# 04-CPU_BOARD.net
KiCad netlist of a schematic drawn in Altium Designer
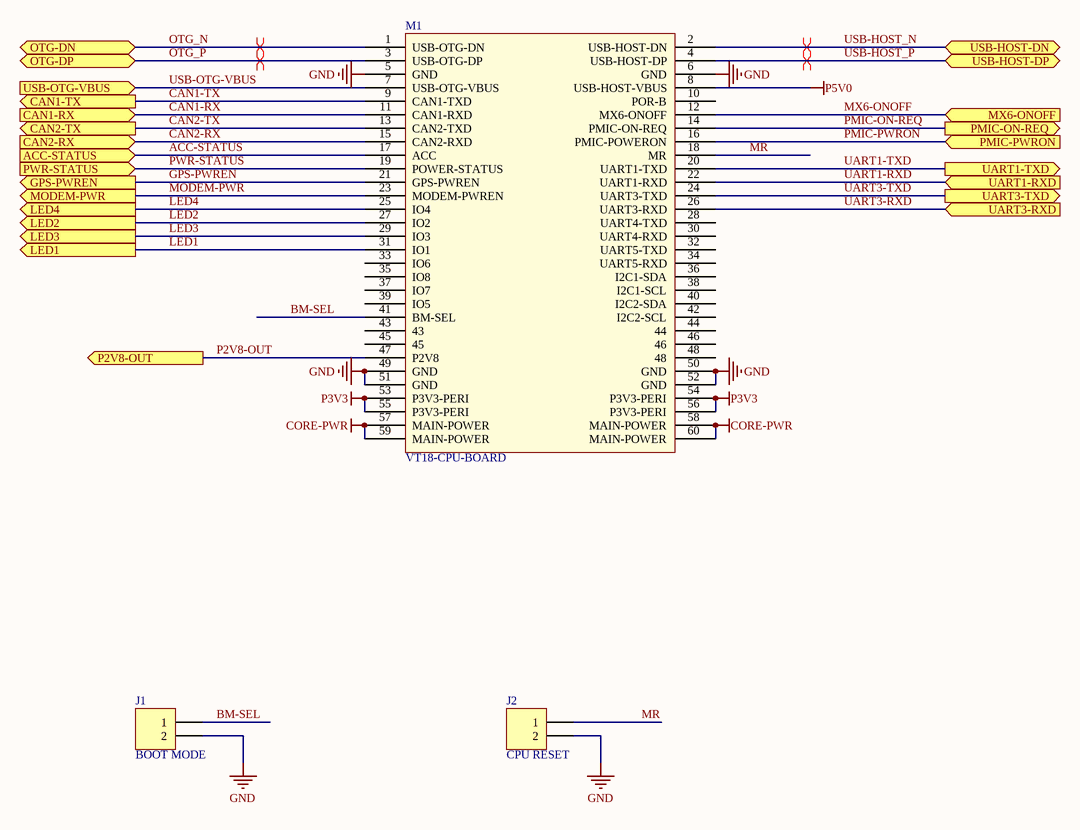
[diagram p0: 04-CPU_BOARD.SchDoc]

(export (version "E")
  (design (tool "Eeschema 10.0.6"))
  (components
    (comp (ref "J1")
      (value "BOOT MODE")
      (footprint "HDR1X2")
      (description "Header, 2-Pin")
      (fields (field (name "PUBLISHER") "Altium Limited"))
      (libsource (lib "Miscellaneous Connectors") (part "Header 2"))
    )
    (comp (ref "J2")
      (value "CPU RESET")
      (footprint "HDR1X2")
      (description "Header, 2-Pin")
      (fields (field (name "PUBLISHER") "Altium Limited"))
      (libsource (lib "Miscellaneous Connectors") (part "Header 2"))
    )
    (comp (ref "M1")
      (value "VT18-CPU-BOARD")
      (footprint "VT18-CPU-BOARD")
      (libsource (lib "Schlib") (part "VT18-CPU-BOARD"))
    )
  )
  (nets
    (net (code "1") (name "/ACC-STATUS") (class "Default")
      (node (ref "M1") (pin "17") (pinfunction "ACC_17") (pintype "passive"))
    )
    (net (code "2") (name "/BM-SEL") (class "Default")
      (node (ref "J1") (pin "1") (pinfunction "1_1") (pintype "passive"))
      (node (ref "M1") (pin "41") (pinfunction "BM-SEL_41") (pintype "passive"))
    )
    (net (code "3") (name "/CAN1-RX") (class "Default")
      (node (ref "M1") (pin "11") (pinfunction "CAN1-RXD_11") (pintype "passive"))
    )
    (net (code "4") (name "/CAN1-TX") (class "Default")
      (node (ref "M1") (pin "9") (pinfunction "CAN1-TXD_9") (pintype "passive"))
    )
    (net (code "5") (name "/CAN2-RX") (class "Default")
      (node (ref "M1") (pin "15") (pinfunction "CAN2-RXD_15") (pintype "passive"))
    )
    (net (code "6") (name "/CAN2-TX") (class "Default")
      (node (ref "M1") (pin "13") (pinfunction "CAN2-TXD_13") (pintype "passive"))
    )
    (net (code "7") (name "/GPS-PWREN") (class "Default")
      (node (ref "M1") (pin "21") (pinfunction "GPS-PWREN_21") (pintype "passive"))
    )
    (net (code "8") (name "/LED1") (class "Default")
      (node (ref "M1") (pin "31") (pinfunction "IO1_31") (pintype "passive"))
    )
    (net (code "9") (name "/LED2") (class "Default")
      (node (ref "M1") (pin "27") (pinfunction "IO2_27") (pintype "passive"))
    )
    (net (code "10") (name "/LED3") (class "Default")
      (node (ref "M1") (pin "29") (pinfunction "IO3_29") (pintype "passive"))
    )
    (net (code "11") (name "/LED4") (class "Default")
      (node (ref "M1") (pin "25") (pinfunction "IO4_25") (pintype "passive"))
    )
    (net (code "12") (name "/MODEM-PWR") (class "Default")
      (node (ref "M1") (pin "23") (pinfunction "MODEM-PWREN_23") (pintype "passive"))
    )
    (net (code "13") (name "/MR") (class "Default")
      (node (ref "J2") (pin "1") (pinfunction "1_1") (pintype "passive"))
      (node (ref "M1") (pin "18") (pinfunction "MR_18") (pintype "passive"))
    )
    (net (code "14") (name "/MX6-ONOFF") (class "Default")
      (node (ref "M1") (pin "12") (pinfunction "MX6-ONOFF_12") (pintype "passive"))
    )
    (net (code "15") (name "/OTG_N") (class "Default")
      (node (ref "M1") (pin "1") (pinfunction "USB-OTG-DN_1") (pintype "passive"))
    )
    (net (code "16") (name "/OTG_P") (class "Default")
      (node (ref "M1") (pin "3") (pinfunction "USB-OTG-DP_3") (pintype "passive"))
    )
    (net (code "17") (name "/P2V8-OUT") (class "Default")
      (node (ref "M1") (pin "47") (pinfunction "P2V8_47") (pintype "passive"))
    )
    (net (code "18") (name "/PMIC-ON-REQ") (class "Default")
      (node (ref "M1") (pin "14") (pinfunction "PMIC-ON-REQ_14") (pintype "passive"))
    )
    (net (code "19") (name "/PMIC-PWRON") (class "Default")
      (node (ref "M1") (pin "16") (pinfunction "PMIC-POWERON_16") (pintype "passive"))
    )
    (net (code "20") (name "/PWR-STATUS") (class "Default")
      (node (ref "M1") (pin "19") (pinfunction "POWER-STATUS_19") (pintype "passive"))
    )
    (net (code "21") (name "/UART1-RXD") (class "Default")
      (node (ref "M1") (pin "22") (pinfunction "UART1-RXD_22") (pintype "passive"))
    )
    (net (code "22") (name "/UART1-TXD") (class "Default")
      (node (ref "M1") (pin "20") (pinfunction "UART1-TXD_20") (pintype "passive"))
    )
    (net (code "23") (name "/UART3-RXD") (class "Default")
      (node (ref "M1") (pin "26") (pinfunction "UART3-RXD_26") (pintype "passive"))
    )
    (net (code "24") (name "/UART3-TXD") (class "Default")
      (node (ref "M1") (pin "24") (pinfunction "UART3-TXD_24") (pintype "passive"))
    )
    (net (code "25") (name "/USB-HOST_N") (class "Default")
      (node (ref "M1") (pin "2") (pinfunction "USB-HOST-DN_2") (pintype "passive"))
    )
    (net (code "26") (name "/USB-HOST_P") (class "Default")
      (node (ref "M1") (pin "4") (pinfunction "USB-HOST-DP_4") (pintype "passive"))
    )
    (net (code "27") (name "/USB-OTG-VBUS") (class "Default")
      (node (ref "M1") (pin "7") (pinfunction "USB-OTG-VBUS_7") (pintype "passive"))
    )
    (net (code "28") (name "CORE-PWR") (class "Default")
      (node (ref "M1") (pin "57") (pinfunction "MAIN-POWER_57") (pintype "passive"))
      (node (ref "M1") (pin "58") (pinfunction "MAIN-POWER_58") (pintype "passive"))
      (node (ref "M1") (pin "59") (pinfunction "MAIN-POWER_59") (pintype "passive"))
      (node (ref "M1") (pin "60") (pinfunction "MAIN-POWER_60") (pintype "passive"))
    )
    (net (code "29") (name "GND") (class "Default")
      (node (ref "J1") (pin "2") (pinfunction "2_2") (pintype "passive"))
      (node (ref "J2") (pin "2") (pinfunction "2_2") (pintype "passive"))
      (node (ref "M1") (pin "49") (pinfunction "GND_49") (pintype "passive"))
      (node (ref "M1") (pin "5") (pinfunction "GND_5") (pintype "passive"))
      (node (ref "M1") (pin "50") (pinfunction "GND_50") (pintype "passive"))
      (node (ref "M1") (pin "51") (pinfunction "GND_51") (pintype "passive"))
      (node (ref "M1") (pin "52") (pinfunction "GND_52") (pintype "passive"))
      (node (ref "M1") (pin "6") (pinfunction "GND_6") (pintype "passive"))
    )
    (net (code "30") (name "P3V3") (class "Default")
      (node (ref "M1") (pin "53") (pinfunction "P3V3-PERI_53") (pintype "passive"))
      (node (ref "M1") (pin "54") (pinfunction "P3V3-PERI_54") (pintype "passive"))
      (node (ref "M1") (pin "55") (pinfunction "P3V3-PERI_55") (pintype "passive"))
      (node (ref "M1") (pin "56") (pinfunction "P3V3-PERI_56") (pintype "passive"))
    )
    (net (code "31") (name "P5V0") (class "Default")
      (node (ref "M1") (pin "8") (pinfunction "USB-HOST-VBUS_8") (pintype "passive"))
    )
    (net (code "32") (name "unconnected-(M1-I2C1-SCL-Pad38)") (class "Default")
      (node (ref "M1") (pin "38") (pinfunction "I2C1-SCL_38") (pintype "passive"))
    )
    (net (code "33") (name "unconnected-(M1-I2C1-SDA-Pad36)") (class "Default")
      (node (ref "M1") (pin "36") (pinfunction "I2C1-SDA_36") (pintype "passive"))
    )
    (net (code "34") (name "unconnected-(M1-I2C2-SCL-Pad42)") (class "Default")
      (node (ref "M1") (pin "42") (pinfunction "I2C2-SCL_42") (pintype "passive"))
    )
    (net (code "35") (name "unconnected-(M1-I2C2-SDA-Pad40)") (class "Default")
      (node (ref "M1") (pin "40") (pinfunction "I2C2-SDA_40") (pintype "passive"))
    )
    (net (code "36") (name "unconnected-(M1-IO5-Pad39)") (class "Default")
      (node (ref "M1") (pin "39") (pinfunction "IO5_39") (pintype "passive"))
    )
    (net (code "37") (name "unconnected-(M1-IO6-Pad33)") (class "Default")
      (node (ref "M1") (pin "33") (pinfunction "IO6_33") (pintype "passive"))
    )
    (net (code "38") (name "unconnected-(M1-IO7-Pad37)") (class "Default")
      (node (ref "M1") (pin "37") (pinfunction "IO7_37") (pintype "passive"))
    )
    (net (code "39") (name "unconnected-(M1-IO8-Pad35)") (class "Default")
      (node (ref "M1") (pin "35") (pinfunction "IO8_35") (pintype "passive"))
    )
    (net (code "40") (name "unconnected-(M1-POR-B-Pad10)") (class "Default")
      (node (ref "M1") (pin "10") (pinfunction "POR-B_10") (pintype "passive"))
    )
    (net (code "41") (name "unconnected-(M1-Pad43)") (class "Default")
      (node (ref "M1") (pin "43") (pinfunction "43_43") (pintype "passive"))
    )
    (net (code "42") (name "unconnected-(M1-Pad44)") (class "Default")
      (node (ref "M1") (pin "44") (pinfunction "44_44") (pintype "passive"))
    )
    (net (code "43") (name "unconnected-(M1-Pad45)") (class "Default")
      (node (ref "M1") (pin "45") (pinfunction "45_45") (pintype "passive"))
    )
    (net (code "44") (name "unconnected-(M1-Pad46)") (class "Default")
      (node (ref "M1") (pin "46") (pinfunction "46_46") (pintype "passive"))
    )
    (net (code "45") (name "unconnected-(M1-Pad48)") (class "Default")
      (node (ref "M1") (pin "48") (pinfunction "48_48") (pintype "passive"))
    )
    (net (code "46") (name "unconnected-(M1-UART4-RXD-Pad30)") (class "Default")
      (node (ref "M1") (pin "30") (pinfunction "UART4-RXD_30") (pintype "passive"))
    )
    (net (code "47") (name "unconnected-(M1-UART4-TXD-Pad28)") (class "Default")
      (node (ref "M1") (pin "28") (pinfunction "UART4-TXD_28") (pintype "passive"))
    )
    (net (code "48") (name "unconnected-(M1-UART5-RXD-Pad34)") (class "Default")
      (node (ref "M1") (pin "34") (pinfunction "UART5-RXD_34") (pintype "passive"))
    )
    (net (code "49") (name "unconnected-(M1-UART5-TXD-Pad32)") (class "Default")
      (node (ref "M1") (pin "32") (pinfunction "UART5-TXD_32") (pintype "passive"))
    )
  )
)
